# 4_Protection.net
KiCad netlist of a schematic drawn in Altium Designer
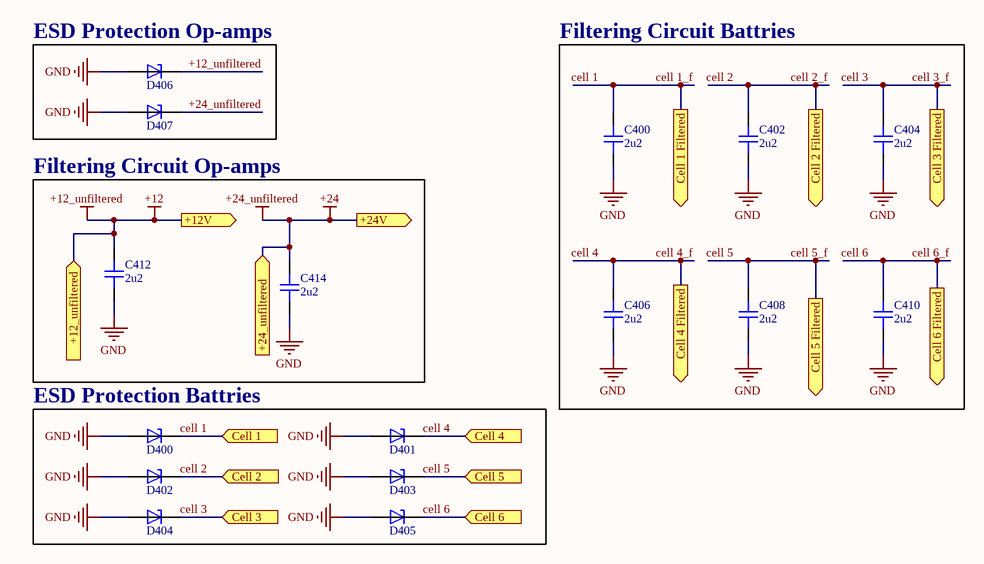
[diagram p0: 4_Protection.SchDoc]

(export (version "E")
  (design (tool "Eeschema 10.0.6"))
  (components
    (comp (ref "C400")
      (value "2u2")
      (footprint "CAP_1206")
      (description "Capacitor SMD 1206")
      (libsource (lib "Schematic-Lib-PhilsLab") (part "CAP_1206"))
    )
    (comp (ref "C402")
      (value "2u2")
      (footprint "CAP_1206")
      (description "Capacitor SMD 1206")
      (libsource (lib "Schematic-Lib-PhilsLab") (part "CAP_1206"))
    )
    (comp (ref "C404")
      (value "2u2")
      (footprint "CAP_1206")
      (description "Capacitor SMD 1206")
      (libsource (lib "Schematic-Lib-PhilsLab") (part "CAP_1206"))
    )
    (comp (ref "C406")
      (value "2u2")
      (footprint "CAP_1206")
      (description "Capacitor SMD 1206")
      (libsource (lib "Schematic-Lib-PhilsLab") (part "CAP_1206"))
    )
    (comp (ref "C408")
      (value "2u2")
      (footprint "CAP_1206")
      (description "Capacitor SMD 1206")
      (libsource (lib "Schematic-Lib-PhilsLab") (part "CAP_1206"))
    )
    (comp (ref "C410")
      (value "2u2")
      (footprint "CAP_1206")
      (description "Capacitor SMD 1206")
      (libsource (lib "Schematic-Lib-PhilsLab") (part "CAP_1206"))
    )
    (comp (ref "C412")
      (value "2u2")
      (footprint "CAP_1206")
      (description "Capacitor SMD 1206")
      (libsource (lib "Schematic-Lib-PhilsLab") (part "CAP_1206"))
    )
    (comp (ref "C414")
      (value "2u2")
      (footprint "CAP_1206")
      (description "Capacitor SMD 1206")
      (libsource (lib "Schematic-Lib-PhilsLab") (part "CAP_1206"))
    )
    (comp (ref "D400")
      (value "TVS-P6KE400A")
      (footprint "TVS")
      (libsource (lib "MIA_LIBRARY") (part "TVS-P6KE400A"))
    )
    (comp (ref "D401")
      (value "TVS-P6KE400A")
      (footprint "TVS")
      (libsource (lib "MIA_LIBRARY") (part "TVS-P6KE400A"))
    )
    (comp (ref "D402")
      (value "TVS-P6KE400A")
      (footprint "TVS")
      (libsource (lib "MIA_LIBRARY") (part "TVS-P6KE400A"))
    )
    (comp (ref "D403")
      (value "TVS-P6KE400A")
      (footprint "TVS")
      (libsource (lib "MIA_LIBRARY") (part "TVS-P6KE400A"))
    )
    (comp (ref "D404")
      (value "TVS-P6KE400A")
      (footprint "TVS")
      (libsource (lib "MIA_LIBRARY") (part "TVS-P6KE400A"))
    )
    (comp (ref "D405")
      (value "TVS-P6KE400A")
      (footprint "TVS")
      (libsource (lib "MIA_LIBRARY") (part "TVS-P6KE400A"))
    )
    (comp (ref "D406")
      (value "TVS-P6KE400A")
      (footprint "TVS")
      (libsource (lib "MIA_LIBRARY") (part "TVS-P6KE400A"))
    )
    (comp (ref "D407")
      (value "TVS-P6KE400A")
      (footprint "TVS")
      (libsource (lib "MIA_LIBRARY") (part "TVS-P6KE400A"))
    )
  )
  (nets
    (net (code "1") (name "+12") (class "Default")
      (node (ref "C412") (pin "2") (pinfunction "2_2") (pintype "passive"))
      (node (ref "D406") (pin "C") (pinfunction "C_C") (pintype "passive"))
    )
    (net (code "2") (name "+24") (class "Default")
      (node (ref "C414") (pin "2") (pinfunction "2_2") (pintype "passive"))
      (node (ref "D407") (pin "C") (pinfunction "C_C") (pintype "passive"))
    )
    (net (code "3") (name "/cell 1") (class "Default")
      (node (ref "C400") (pin "2") (pinfunction "2_2") (pintype "passive"))
      (node (ref "D400") (pin "C") (pinfunction "C_C") (pintype "passive"))
    )
    (net (code "4") (name "/cell 2") (class "Default")
      (node (ref "C402") (pin "2") (pinfunction "2_2") (pintype "passive"))
      (node (ref "D402") (pin "C") (pinfunction "C_C") (pintype "passive"))
    )
    (net (code "5") (name "/cell 3") (class "Default")
      (node (ref "C404") (pin "2") (pinfunction "2_2") (pintype "passive"))
      (node (ref "D404") (pin "C") (pinfunction "C_C") (pintype "passive"))
    )
    (net (code "6") (name "/cell 4") (class "Default")
      (node (ref "C406") (pin "2") (pinfunction "2_2") (pintype "passive"))
      (node (ref "D401") (pin "C") (pinfunction "C_C") (pintype "passive"))
    )
    (net (code "7") (name "/cell 5") (class "Default")
      (node (ref "C408") (pin "2") (pinfunction "2_2") (pintype "passive"))
      (node (ref "D403") (pin "C") (pinfunction "C_C") (pintype "passive"))
    )
    (net (code "8") (name "/cell 6") (class "Default")
      (node (ref "C410") (pin "2") (pinfunction "2_2") (pintype "passive"))
      (node (ref "D405") (pin "C") (pinfunction "C_C") (pintype "passive"))
    )
    (net (code "9") (name "GND") (class "Default")
      (node (ref "C400") (pin "1") (pinfunction "1_1") (pintype "passive"))
      (node (ref "C402") (pin "1") (pinfunction "1_1") (pintype "passive"))
      (node (ref "C404") (pin "1") (pinfunction "1_1") (pintype "passive"))
      (node (ref "C406") (pin "1") (pinfunction "1_1") (pintype "passive"))
      (node (ref "C408") (pin "1") (pinfunction "1_1") (pintype "passive"))
      (node (ref "C410") (pin "1") (pinfunction "1_1") (pintype "passive"))
      (node (ref "C412") (pin "1") (pinfunction "1_1") (pintype "passive"))
      (node (ref "C414") (pin "1") (pinfunction "1_1") (pintype "passive"))
      (node (ref "D400") (pin "A") (pinfunction "A_A") (pintype "passive"))
      (node (ref "D401") (pin "A") (pinfunction "A_A") (pintype "passive"))
      (node (ref "D402") (pin "A") (pinfunction "A_A") (pintype "passive"))
      (node (ref "D403") (pin "A") (pinfunction "A_A") (pintype "passive"))
      (node (ref "D404") (pin "A") (pinfunction "A_A") (pintype "passive"))
      (node (ref "D405") (pin "A") (pinfunction "A_A") (pintype "passive"))
      (node (ref "D406") (pin "A") (pinfunction "A_A") (pintype "passive"))
      (node (ref "D407") (pin "A") (pinfunction "A_A") (pintype "passive"))
    )
  )
)
